# RGB_Lanyard_Driver_Schematic.net
KiCad netlist of a schematic drawn in EAGLE
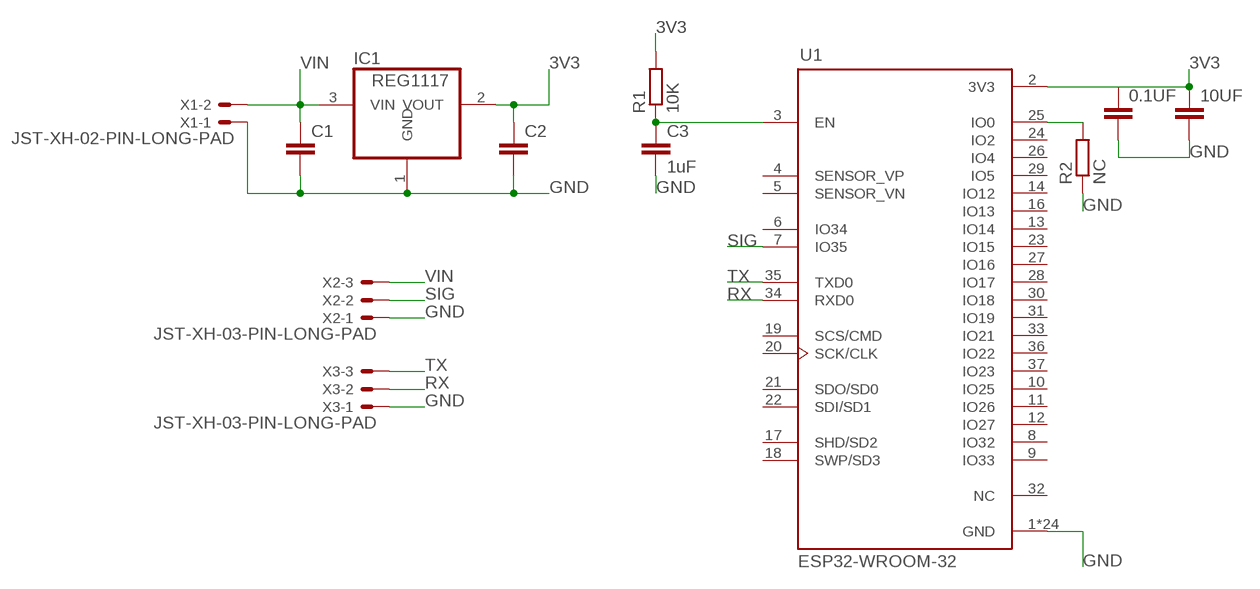
[diagram p0: schematic, sheet 1]

(export (version "E")
  (design (tool "Eeschema 10.0.6"))
  (components
    (comp (ref "0.1UF")
      (value "C-EUC0805")
      (footprint "eagle-import:C0805")
      (libsource (lib "eagle-import") (part "C-EUC0805"))
    )
    (comp (ref "10UF")
      (value "C-EUC0805")
      (footprint "eagle-import:C0805")
      (libsource (lib "eagle-import") (part "C-EUC0805"))
    )
    (comp (ref "C1")
      (value "C-EUC0805")
      (footprint "eagle-import:C0805")
      (libsource (lib "eagle-import") (part "C-EUC0805"))
    )
    (comp (ref "C2")
      (value "C-EUC0805")
      (footprint "eagle-import:C0805")
      (libsource (lib "eagle-import") (part "C-EUC0805"))
    )
    (comp (ref "C3")
      (value "1uF")
      (footprint "eagle-import:C0805")
      (libsource (lib "eagle-import") (part "C-EUC0805"))
    )
    (comp (ref "IC1")
      (value "REG1117")
      (footprint "eagle-import:SOT223")
      (libsource (lib "eagle-import") (part "REG1117"))
    )
    (comp (ref "R1")
      (value "10K")
      (footprint "eagle-import:R0805")
      (libsource (lib "eagle-import") (part "R-EU_R0805"))
    )
    (comp (ref "R2")
      (value "NC")
      (footprint "eagle-import:R0805")
      (libsource (lib "eagle-import") (part "R-EU_R0805"))
    )
    (comp (ref "U1")
      (value "ESP32-WROOM-32")
      (footprint "eagle-import:MODULE_ESP32-WROOM-32")
      (fields (field (name "MF") "Espressif Systems"))
      (libsource (lib "eagle-import") (part "ESP32-WROOM-32"))
    )
    (comp (ref "X1")
      (value "JST-XH-02-PIN-LONG-PAD")
      (footprint "eagle-import:JST-XH-02-PACKAGE-LONG-PAD")
      (libsource (lib "eagle-import") (part "JST-XH-02-PIN-LONG-PAD"))
    )
    (comp (ref "X2")
      (value "JST-XH-03-PIN-LONG-PAD")
      (footprint "eagle-import:JST-XH-03-PACKAGE-LONG-PAD")
      (libsource (lib "eagle-import") (part "JST-XH-03-PIN-LONG-PAD"))
    )
    (comp (ref "X3")
      (value "JST-XH-03-PIN-LONG-PAD")
      (footprint "eagle-import:JST-XH-03-PACKAGE-LONG-PAD")
      (libsource (lib "eagle-import") (part "JST-XH-03-PIN-LONG-PAD"))
    )
  )
  (nets
    (net (code "1") (name "/3V3") (class "Default")
      (node (ref "0.1UF") (pin "1") (pinfunction "1_1") (pintype "passive"))
      (node (ref "10UF") (pin "1") (pinfunction "1_1") (pintype "passive"))
      (node (ref "C2") (pin "1") (pinfunction "1_1") (pintype "passive"))
      (node (ref "IC1") (pin "2") (pinfunction "VOUT_2") (pintype "output"))
      (node (ref "R1") (pin "2") (pinfunction "2_2") (pintype "passive"))
      (node (ref "U1") (pin "2") (pinfunction "3V3_2") (pintype "power_in"))
    )
    (net (code "2") (name "/GND") (class "Default")
      (node (ref "0.1UF") (pin "2") (pinfunction "2_2") (pintype "passive"))
      (node (ref "10UF") (pin "2") (pinfunction "2_2") (pintype "passive"))
      (node (ref "C1") (pin "2") (pinfunction "2_2") (pintype "passive"))
      (node (ref "C2") (pin "2") (pinfunction "2_2") (pintype "passive"))
      (node (ref "C3") (pin "2") (pinfunction "2_2") (pintype "passive"))
      (node (ref "IC1") (pin "1") (pinfunction "GND_1") (pintype "power_in"))
      (node (ref "R2") (pin "1") (pinfunction "1_1") (pintype "passive"))
      (node (ref "U1") (pin "1") (pinfunction "GND_1") (pintype "power_in"))
      (node (ref "U1") (pin "15") (pinfunction "GND_15") (pintype "power_in"))
      (node (ref "U1") (pin "38") (pinfunction "GND_38") (pintype "power_in"))
      (node (ref "U1") (pin "39_1") (pinfunction "GND_39_1") (pintype "power_in"))
      (node (ref "U1") (pin "39_10") (pinfunction "GND_39_10") (pintype "power_in"))
      (node (ref "U1") (pin "39_11") (pinfunction "GND_39_11") (pintype "power_in"))
      (node (ref "U1") (pin "39_12") (pinfunction "GND_39_12") (pintype "power_in"))
      (node (ref "U1") (pin "39_13") (pinfunction "GND_39_13") (pintype "power_in"))
      (node (ref "U1") (pin "39_14") (pinfunction "GND_39_14") (pintype "power_in"))
      (node (ref "U1") (pin "39_15") (pinfunction "GND_39_15") (pintype "power_in"))
      (node (ref "U1") (pin "39_16") (pinfunction "GND_39_16") (pintype "power_in"))
      (node (ref "U1") (pin "39_17") (pinfunction "GND_39_17") (pintype "power_in"))
      (node (ref "U1") (pin "39_18") (pinfunction "GND_39_18") (pintype "power_in"))
      (node (ref "U1") (pin "39_19") (pinfunction "GND_39_19") (pintype "power_in"))
      (node (ref "U1") (pin "39_2") (pinfunction "GND_39_2") (pintype "power_in"))
      (node (ref "U1") (pin "39_20") (pinfunction "GND_39_20") (pintype "power_in"))
      (node (ref "U1") (pin "39_21") (pinfunction "GND_39_21") (pintype "power_in"))
      (node (ref "U1") (pin "39_3") (pinfunction "GND_39_3") (pintype "power_in"))
      (node (ref "U1") (pin "39_4") (pinfunction "GND_39_4") (pintype "power_in"))
      (node (ref "U1") (pin "39_5") (pinfunction "GND_39_5") (pintype "power_in"))
      (node (ref "U1") (pin "39_6") (pinfunction "GND_39_6") (pintype "power_in"))
      (node (ref "U1") (pin "39_7") (pinfunction "GND_39_7") (pintype "power_in"))
      (node (ref "U1") (pin "39_8") (pinfunction "GND_39_8") (pintype "power_in"))
      (node (ref "U1") (pin "39_9") (pinfunction "GND_39_9") (pintype "power_in"))
      (node (ref "X1") (pin "1") (pinfunction "S_1") (pintype "passive"))
      (node (ref "X2") (pin "1") (pinfunction "S_1") (pintype "passive"))
      (node (ref "X3") (pin "1") (pinfunction "S_1") (pintype "passive"))
    )
    (net (code "3") (name "/RX") (class "Default")
      (node (ref "U1") (pin "34") (pinfunction "RXD0_34") (pintype "bidirectional"))
      (node (ref "X3") (pin "2") (pinfunction "S_2") (pintype "passive"))
    )
    (net (code "4") (name "/SIG") (class "Default")
      (node (ref "U1") (pin "7") (pinfunction "IO35_7") (pintype "input"))
      (node (ref "X2") (pin "2") (pinfunction "S_2") (pintype "passive"))
    )
    (net (code "5") (name "/TX") (class "Default")
      (node (ref "U1") (pin "35") (pinfunction "TXD0_35") (pintype "bidirectional"))
      (node (ref "X3") (pin "3") (pinfunction "S_3") (pintype "passive"))
    )
    (net (code "6") (name "/VIN") (class "Default")
      (node (ref "C1") (pin "1") (pinfunction "1_1") (pintype "passive"))
      (node (ref "IC1") (pin "3") (pinfunction "VIN_3") (pintype "input"))
      (node (ref "X1") (pin "2") (pinfunction "S_2") (pintype "passive"))
      (node (ref "X2") (pin "3") (pinfunction "S_3") (pintype "passive"))
    )
    (net (code "7") (name "Net-(U1-EN)") (class "Default")
      (node (ref "C3") (pin "1") (pinfunction "1_1") (pintype "passive"))
      (node (ref "R1") (pin "1") (pinfunction "1_1") (pintype "passive"))
      (node (ref "U1") (pin "3") (pinfunction "EN_3") (pintype "input"))
    )
    (net (code "8") (name "Net-(U1-IO0)") (class "Default")
      (node (ref "R2") (pin "2") (pinfunction "2_2") (pintype "passive"))
      (node (ref "U1") (pin "25") (pinfunction "IO0_25") (pintype "bidirectional"))
    )
    (net (code "9") (name "unconnected-(U1-IO2-Pad24)") (class "Default")
      (node (ref "U1") (pin "24") (pinfunction "IO2_24") (pintype "bidirectional"))
    )
    (net (code "10") (name "unconnected-(U1-IO4-Pad26)") (class "Default")
      (node (ref "U1") (pin "26") (pinfunction "IO4_26") (pintype "bidirectional"))
    )
    (net (code "11") (name "unconnected-(U1-IO5-Pad29)") (class "Default")
      (node (ref "U1") (pin "29") (pinfunction "IO5_29") (pintype "bidirectional"))
    )
    (net (code "12") (name "unconnected-(U1-IO12-Pad14)") (class "Default")
      (node (ref "U1") (pin "14") (pinfunction "IO12_14") (pintype "bidirectional"))
    )
    (net (code "13") (name "unconnected-(U1-IO13-Pad16)") (class "Default")
      (node (ref "U1") (pin "16") (pinfunction "IO13_16") (pintype "bidirectional"))
    )
    (net (code "14") (name "unconnected-(U1-IO14-Pad13)") (class "Default")
      (node (ref "U1") (pin "13") (pinfunction "IO14_13") (pintype "bidirectional"))
    )
    (net (code "15") (name "unconnected-(U1-IO15-Pad23)") (class "Default")
      (node (ref "U1") (pin "23") (pinfunction "IO15_23") (pintype "bidirectional"))
    )
    (net (code "16") (name "unconnected-(U1-IO16-Pad27)") (class "Default")
      (node (ref "U1") (pin "27") (pinfunction "IO16_27") (pintype "bidirectional"))
    )
    (net (code "17") (name "unconnected-(U1-IO17-Pad28)") (class "Default")
      (node (ref "U1") (pin "28") (pinfunction "IO17_28") (pintype "bidirectional"))
    )
    (net (code "18") (name "unconnected-(U1-IO18-Pad30)") (class "Default")
      (node (ref "U1") (pin "30") (pinfunction "IO18_30") (pintype "bidirectional"))
    )
    (net (code "19") (name "unconnected-(U1-IO19-Pad31)") (class "Default")
      (node (ref "U1") (pin "31") (pinfunction "IO19_31") (pintype "bidirectional"))
    )
    (net (code "20") (name "unconnected-(U1-IO21-Pad33)") (class "Default")
      (node (ref "U1") (pin "33") (pinfunction "IO21_33") (pintype "bidirectional"))
    )
    (net (code "21") (name "unconnected-(U1-IO22-Pad36)") (class "Default")
      (node (ref "U1") (pin "36") (pinfunction "IO22_36") (pintype "bidirectional"))
    )
    (net (code "22") (name "unconnected-(U1-IO23-Pad37)") (class "Default")
      (node (ref "U1") (pin "37") (pinfunction "IO23_37") (pintype "bidirectional"))
    )
    (net (code "23") (name "unconnected-(U1-IO25-Pad10)") (class "Default")
      (node (ref "U1") (pin "10") (pinfunction "IO25_10") (pintype "bidirectional"))
    )
    (net (code "24") (name "unconnected-(U1-IO26-Pad11)") (class "Default")
      (node (ref "U1") (pin "11") (pinfunction "IO26_11") (pintype "bidirectional"))
    )
    (net (code "25") (name "unconnected-(U1-IO27-Pad12)") (class "Default")
      (node (ref "U1") (pin "12") (pinfunction "IO27_12") (pintype "bidirectional"))
    )
    (net (code "26") (name "unconnected-(U1-IO32-Pad8)") (class "Default")
      (node (ref "U1") (pin "8") (pinfunction "IO32_8") (pintype "bidirectional"))
    )
    (net (code "27") (name "unconnected-(U1-IO33-Pad9)") (class "Default")
      (node (ref "U1") (pin "9") (pinfunction "IO33_9") (pintype "bidirectional"))
    )
    (net (code "28") (name "unconnected-(U1-IO34-Pad6)") (class "Default")
      (node (ref "U1") (pin "6") (pinfunction "IO34_6") (pintype "input"))
    )
    (net (code "29") (name "unconnected-(U1-NC-Pad32)") (class "Default")
      (node (ref "U1") (pin "32") (pinfunction "NC_32") (pintype "no_connect"))
    )
    (net (code "30") (name "unconnected-(U1-SCK{slash}CLK-Pad20)") (class "Default")
      (node (ref "U1") (pin "20") (pinfunction "SCK/CLK_20") (pintype "bidirectional"))
    )
    (net (code "31") (name "unconnected-(U1-SCS{slash}CMD-Pad19)") (class "Default")
      (node (ref "U1") (pin "19") (pinfunction "SCS/CMD_19") (pintype "bidirectional"))
    )
    (net (code "32") (name "unconnected-(U1-SDI{slash}SD1-Pad22)") (class "Default")
      (node (ref "U1") (pin "22") (pinfunction "SDI/SD1_22") (pintype "bidirectional"))
    )
    (net (code "33") (name "unconnected-(U1-SDO{slash}SD0-Pad21)") (class "Default")
      (node (ref "U1") (pin "21") (pinfunction "SDO/SD0_21") (pintype "bidirectional"))
    )
    (net (code "34") (name "unconnected-(U1-SENSOR_VN-Pad5)") (class "Default")
      (node (ref "U1") (pin "5") (pinfunction "SENSOR_VN_5") (pintype "input"))
    )
    (net (code "35") (name "unconnected-(U1-SENSOR_VP-Pad4)") (class "Default")
      (node (ref "U1") (pin "4") (pinfunction "SENSOR_VP_4") (pintype "input"))
    )
    (net (code "36") (name "unconnected-(U1-SHD{slash}SD2-Pad17)") (class "Default")
      (node (ref "U1") (pin "17") (pinfunction "SHD/SD2_17") (pintype "bidirectional"))
    )
    (net (code "37") (name "unconnected-(U1-SWP{slash}SD3-Pad18)") (class "Default")
      (node (ref "U1") (pin "18") (pinfunction "SWP/SD3_18") (pintype "bidirectional"))
    )
  )
)
